# NightLightWiring.net
KiCad netlist of a schematic drawn in EAGLE
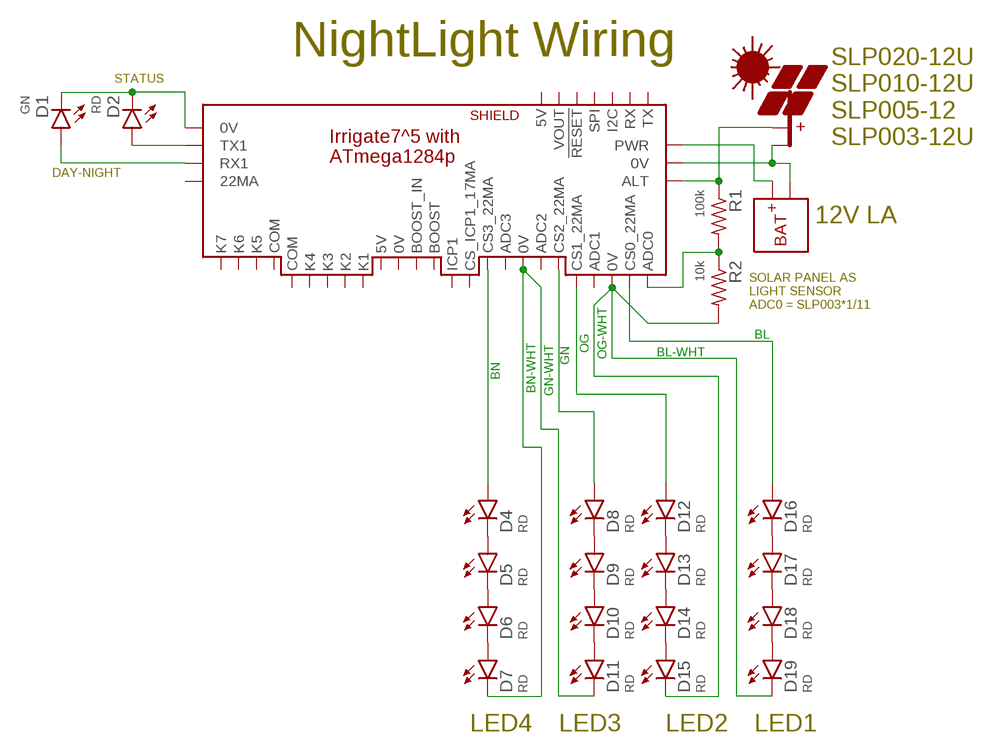
[diagram p0: schematic, sheet 1]

(export (version "E")
  (design (tool "Eeschema 10.0.6"))
  (components
    (comp (ref "D1")
      (value "GN")
      (footprint "eagle-import:LED5MM")
      (libsource (lib "eagle-import") (part "LED5MM"))
    )
    (comp (ref "D2")
      (value "RD")
      (footprint "eagle-import:LED5MM")
      (libsource (lib "eagle-import") (part "LED5MM"))
    )
    (comp (ref "D4")
      (value "RD")
      (footprint "eagle-import:LED5MM")
      (libsource (lib "eagle-import") (part "LED5MM"))
    )
    (comp (ref "D5")
      (value "RD")
      (footprint "eagle-import:LED5MM")
      (libsource (lib "eagle-import") (part "LED5MM"))
    )
    (comp (ref "D6")
      (value "RD")
      (footprint "eagle-import:LED5MM")
      (libsource (lib "eagle-import") (part "LED5MM"))
    )
    (comp (ref "D7")
      (value "RD")
      (footprint "eagle-import:LED5MM")
      (libsource (lib "eagle-import") (part "LED5MM"))
    )
    (comp (ref "D8")
      (value "RD")
      (footprint "eagle-import:LED5MM")
      (libsource (lib "eagle-import") (part "LED5MM"))
    )
    (comp (ref "D9")
      (value "RD")
      (footprint "eagle-import:LED5MM")
      (libsource (lib "eagle-import") (part "LED5MM"))
    )
    (comp (ref "D10")
      (value "RD")
      (footprint "eagle-import:LED5MM")
      (libsource (lib "eagle-import") (part "LED5MM"))
    )
    (comp (ref "D11")
      (value "RD")
      (footprint "eagle-import:LED5MM")
      (libsource (lib "eagle-import") (part "LED5MM"))
    )
    (comp (ref "D12")
      (value "RD")
      (footprint "eagle-import:LED5MM")
      (libsource (lib "eagle-import") (part "LED5MM"))
    )
    (comp (ref "D13")
      (value "RD")
      (footprint "eagle-import:LED5MM")
      (libsource (lib "eagle-import") (part "LED5MM"))
    )
    (comp (ref "D14")
      (value "RD")
      (footprint "eagle-import:LED5MM")
      (libsource (lib "eagle-import") (part "LED5MM"))
    )
    (comp (ref "D15")
      (value "RD")
      (footprint "eagle-import:LED5MM")
      (libsource (lib "eagle-import") (part "LED5MM"))
    )
    (comp (ref "D16")
      (value "RD")
      (footprint "eagle-import:LED5MM")
      (libsource (lib "eagle-import") (part "LED5MM"))
    )
    (comp (ref "D17")
      (value "RD")
      (footprint "eagle-import:LED5MM")
      (libsource (lib "eagle-import") (part "LED5MM"))
    )
    (comp (ref "D18")
      (value "RD")
      (footprint "eagle-import:LED5MM")
      (libsource (lib "eagle-import") (part "LED5MM"))
    )
    (comp (ref "D19")
      (value "RD")
      (footprint "eagle-import:LED5MM")
      (libsource (lib "eagle-import") (part "LED5MM"))
    )
    (comp (ref "PV4")
      (value "PV")
      (footprint "eagle-import:NA-30")
      (libsource (lib "eagle-import") (part "PV"))
    )
    (comp (ref "R1")
      (value "100k")
      (footprint "eagle-import:C0805(2012)")
      (libsource (lib "eagle-import") (part "R0805"))
    )
    (comp (ref "R2")
      (value "10k")
      (footprint "eagle-import:C0805(2012)")
      (libsource (lib "eagle-import") (part "R0805"))
    )
    (comp (ref "U$1")
      (value "IRRIGATE7")
      (footprint "eagle-import:WITH_RPU_NAMES")
      (libsource (lib "eagle-import") (part "IRRIGATE7"))
    )
    (comp (ref "U$7")
      (value "BAT")
      (footprint "eagle-import:NA-30")
      (libsource (lib "eagle-import") (part "BAT"))
    )
  )
  (nets
    (net (code "1") (name "/BL") (class "Default")
      (node (ref "D16") (pin "A") (pinfunction "A_A") (pintype "passive"))
      (node (ref "U$1") (pin "22MA@ADC0") (pinfunction "CS0_22MA_22MA@ADC0") (pintype "bidirectional"))
    )
    (net (code "2") (name "/BL-WHT") (class "Default")
      (node (ref "D19") (pin "K") (pinfunction "K_K") (pintype "passive"))
    )
    (net (code "3") (name "/BN") (class "Default")
      (node (ref "D4") (pin "A") (pinfunction "A_A") (pintype "passive"))
      (node (ref "U$1") (pin "22MA@ADC5") (pinfunction "CS3_22MA_22MA@ADC5") (pintype "bidirectional"))
    )
    (net (code "4") (name "/BN-WHT") (class "Default")
      (node (ref "D7") (pin "K") (pinfunction "K_K") (pintype "passive"))
    )
    (net (code "5") (name "/GN") (class "Default")
      (node (ref "D8") (pin "A") (pinfunction "A_A") (pintype "passive"))
      (node (ref "U$1") (pin "22MA@ADC4") (pinfunction "CS2_22MA_22MA@ADC4") (pintype "bidirectional"))
    )
    (net (code "6") (name "/GN-WHT") (class "Default")
      (node (ref "D11") (pin "K") (pinfunction "K_K") (pintype "passive"))
      (node (ref "U$1") (pin "ICP3") (pinfunction "0V_ICP3") (pintype "bidirectional"))
    )
    (net (code "7") (name "/OG") (class "Default")
      (node (ref "D12") (pin "A") (pinfunction "A_A") (pintype "passive"))
      (node (ref "U$1") (pin "22MA@ADC1") (pinfunction "CS1_22MA_22MA@ADC1") (pintype "bidirectional"))
    )
    (net (code "8") (name "/OG-WHT") (class "Default")
      (node (ref "D15") (pin "K") (pinfunction "K_K") (pintype "passive"))
      (node (ref "U$1") (pin "0V@ADC2") (pinfunction "0V_0V@ADC2") (pintype "bidirectional"))
    )
    (net (code "9") (name "Net-(D1-PadK)") (class "Default")
      (node (ref "D1") (pin "K") (pinfunction "K_K") (pintype "passive"))
      (node (ref "D2") (pin "K") (pinfunction "K_K") (pintype "passive"))
      (node (ref "U$1") (pin "17MA@ICP3") (pinfunction "0V_17MA@ICP3") (pintype "bidirectional"))
    )
    (net (code "10") (name "Net-(D4-PadK)") (class "Default")
      (node (ref "D4") (pin "K") (pinfunction "K_K") (pintype "passive"))
      (node (ref "D5") (pin "A") (pinfunction "A_A") (pintype "passive"))
    )
    (net (code "11") (name "Net-(D5-PadK)") (class "Default")
      (node (ref "D5") (pin "K") (pinfunction "K_K") (pintype "passive"))
      (node (ref "D6") (pin "A") (pinfunction "A_A") (pintype "passive"))
    )
    (net (code "12") (name "Net-(D6-PadK)") (class "Default")
      (node (ref "D6") (pin "K") (pinfunction "K_K") (pintype "passive"))
      (node (ref "D7") (pin "A") (pinfunction "A_A") (pintype "passive"))
    )
    (net (code "13") (name "Net-(D8-PadK)") (class "Default")
      (node (ref "D8") (pin "K") (pinfunction "K_K") (pintype "passive"))
      (node (ref "D9") (pin "A") (pinfunction "A_A") (pintype "passive"))
    )
    (net (code "14") (name "Net-(D10-PadA)") (class "Default")
      (node (ref "D10") (pin "A") (pinfunction "A_A") (pintype "passive"))
      (node (ref "D9") (pin "K") (pinfunction "K_K") (pintype "passive"))
    )
    (net (code "15") (name "Net-(D10-PadK)") (class "Default")
      (node (ref "D10") (pin "K") (pinfunction "K_K") (pintype "passive"))
      (node (ref "D11") (pin "A") (pinfunction "A_A") (pintype "passive"))
    )
    (net (code "16") (name "Net-(D12-PadK)") (class "Default")
      (node (ref "D12") (pin "K") (pinfunction "K_K") (pintype "passive"))
      (node (ref "D13") (pin "A") (pinfunction "A_A") (pintype "passive"))
    )
    (net (code "17") (name "Net-(D13-PadK)") (class "Default")
      (node (ref "D13") (pin "K") (pinfunction "K_K") (pintype "passive"))
      (node (ref "D14") (pin "A") (pinfunction "A_A") (pintype "passive"))
    )
    (net (code "18") (name "Net-(D14-PadK)") (class "Default")
      (node (ref "D14") (pin "K") (pinfunction "K_K") (pintype "passive"))
      (node (ref "D15") (pin "A") (pinfunction "A_A") (pintype "passive"))
    )
    (net (code "19") (name "Net-(D16-PadK)") (class "Default")
      (node (ref "D16") (pin "K") (pinfunction "K_K") (pintype "passive"))
      (node (ref "D17") (pin "A") (pinfunction "A_A") (pintype "passive"))
    )
    (net (code "20") (name "Net-(D17-PadK)") (class "Default")
      (node (ref "D17") (pin "K") (pinfunction "K_K") (pintype "passive"))
      (node (ref "D18") (pin "A") (pinfunction "A_A") (pintype "passive"))
    )
    (net (code "21") (name "Net-(D18-PadK)") (class "Default")
      (node (ref "D18") (pin "K") (pinfunction "K_K") (pintype "passive"))
      (node (ref "D19") (pin "A") (pinfunction "A_A") (pintype "passive"))
    )
    (net (code "22") (name "Net-(PV4-+PV)") (class "Default")
      (node (ref "PV4") (pin "1") (pinfunction "+PV_1") (pintype "bidirectional"))
      (node (ref "R1") (pin "1") (pinfunction "1_1") (pintype "passive"))
      (node (ref "U$1") (pin "AUX") (pinfunction "ALT_AUX") (pintype "bidirectional"))
    )
    (net (code "23") (name "Net-(PV4--PV)") (class "Default")
      (node (ref "PV4") (pin "2") (pinfunction "-PV_2") (pintype "bidirectional"))
      (node (ref "U$1") (pin "0V@PWR") (pinfunction "0V_0V@PWR") (pintype "bidirectional"))
      (node (ref "U$7") (pin "2") (pinfunction "-BAT_2") (pintype "bidirectional"))
    )
    (net (code "24") (name "Net-(R1-Pad2)") (class "Default")
      (node (ref "R1") (pin "2") (pinfunction "2_2") (pintype "passive"))
      (node (ref "R2") (pin "1") (pinfunction "1_1") (pintype "passive"))
      (node (ref "U$1") (pin "ADC0") (pinfunction "ADC0_ADC0") (pintype "bidirectional"))
    )
    (net (code "25") (name "Net-(U$1-RX1)") (class "Default")
      (node (ref "D1") (pin "A") (pinfunction "A_A") (pintype "passive"))
      (node (ref "U$1") (pin "DIO2") (pinfunction "RX1_DIO2") (pintype "bidirectional"))
    )
    (net (code "26") (name "Net-(U$1-TX1)") (class "Default")
      (node (ref "D2") (pin "A") (pinfunction "A_A") (pintype "passive"))
      (node (ref "U$1") (pin "DIO3") (pinfunction "TX1_DIO3") (pintype "bidirectional"))
    )
    (net (code "27") (name "Net-(U$7-+BAT)") (class "Default")
      (node (ref "U$1") (pin "PWR") (pinfunction "PWR_PWR") (pintype "bidirectional"))
      (node (ref "U$7") (pin "1") (pinfunction "+BAT_1") (pintype "bidirectional"))
    )
    (net (code "28") (name "unconnected-(R2-Pad2)") (class "Default")
      (node (ref "R2") (pin "2") (pinfunction "2_2") (pintype "passive"))
    )
    (net (code "29") (name "unconnected-(U$1-5V-PadSHLD_5V)") (class "Default")
      (node (ref "U$1") (pin "SHLD_5V") (pinfunction "5V_SHLD_5V") (pintype "bidirectional"))
    )
    (net (code "30") (name "unconnected-(U$1-22MA-Pad22MA@DIO2)") (class "Default")
      (node (ref "U$1") (pin "22MA@DIO2") (pinfunction "22MA_22MA@DIO2") (pintype "bidirectional"))
    )
    (net (code "31") (name "unconnected-(U$1-ADC2-PadADC4)") (class "Default")
      (node (ref "U$1") (pin "ADC4") (pinfunction "ADC2_ADC4") (pintype "bidirectional"))
    )
    (net (code "32") (name "unconnected-(U$1-ADC3-PadADC5)") (class "Default")
      (node (ref "U$1") (pin "ADC5") (pinfunction "ADC3_ADC5") (pintype "bidirectional"))
    )
    (net (code "33") (name "unconnected-(U$1-COM-PadCOM@K4)") (class "Default")
      (node (ref "U$1") (pin "COM@K4") (pinfunction "COM_COM@K4") (pintype "bidirectional"))
    )
    (net (code "34") (name "unconnected-(U$1-COM-PadCOM@K5)") (class "Default")
      (node (ref "U$1") (pin "COM@K5") (pinfunction "COM_COM@K5") (pintype "bidirectional"))
    )
    (net (code "35") (name "unconnected-(U$1-CS_ICP1_17MA-Pad17MA@ICP1)") (class "Default")
      (node (ref "U$1") (pin "17MA@ICP1") (pinfunction "CS_ICP1_17MA_17MA@ICP1") (pintype "bidirectional"))
    )
    (net (code "36") (name "unconnected-(U$1-Pad0V)") (class "Default")
      (node (ref "U$1") (pin "0V") (pinfunction "0V_0V") (pintype "bidirectional"))
    )
    (net (code "37") (name "unconnected-(U$1-Pad5V)") (class "Default")
      (node (ref "U$1") (pin "5V") (pinfunction "5V_5V") (pintype "bidirectional"))
    )
    (net (code "38") (name "unconnected-(U$1-PadADC1)") (class "Default")
      (node (ref "U$1") (pin "ADC1") (pinfunction "ADC1_ADC1") (pintype "bidirectional"))
    )
    (net (code "39") (name "unconnected-(U$1-PadBOOST)") (class "Default")
      (node (ref "U$1") (pin "BOOST") (pinfunction "BOOST_BOOST") (pintype "bidirectional"))
    )
    (net (code "40") (name "unconnected-(U$1-PadBOOST_IN)") (class "Default")
      (node (ref "U$1") (pin "BOOST_IN") (pinfunction "BOOST_IN_BOOST_IN") (pintype "bidirectional"))
    )
    (net (code "41") (name "unconnected-(U$1-PadI2C)") (class "Default")
      (node (ref "U$1") (pin "I2C") (pinfunction "I2C_I2C") (pintype "bidirectional"))
    )
    (net (code "42") (name "unconnected-(U$1-PadICP1)") (class "Default")
      (node (ref "U$1") (pin "ICP1") (pinfunction "ICP1_ICP1") (pintype "bidirectional"))
    )
    (net (code "43") (name "unconnected-(U$1-PadK1)") (class "Default")
      (node (ref "U$1") (pin "K1") (pinfunction "K1_K1") (pintype "bidirectional"))
    )
    (net (code "44") (name "unconnected-(U$1-PadK2)") (class "Default")
      (node (ref "U$1") (pin "K2") (pinfunction "K2_K2") (pintype "bidirectional"))
    )
    (net (code "45") (name "unconnected-(U$1-PadK3)") (class "Default")
      (node (ref "U$1") (pin "K3") (pinfunction "K3_K3") (pintype "bidirectional"))
    )
    (net (code "46") (name "unconnected-(U$1-PadK4)") (class "Default")
      (node (ref "U$1") (pin "K4") (pinfunction "K4_K4") (pintype "bidirectional"))
    )
    (net (code "47") (name "unconnected-(U$1-PadK5)") (class "Default")
      (node (ref "U$1") (pin "K5") (pinfunction "K5_K5") (pintype "bidirectional"))
    )
    (net (code "48") (name "unconnected-(U$1-PadK6)") (class "Default")
      (node (ref "U$1") (pin "K6") (pinfunction "K6_K6") (pintype "bidirectional"))
    )
    (net (code "49") (name "unconnected-(U$1-PadK7)") (class "Default")
      (node (ref "U$1") (pin "K7") (pinfunction "K7_K7") (pintype "bidirectional"))
    )
    (net (code "50") (name "unconnected-(U$1-PadRX)") (class "Default")
      (node (ref "U$1") (pin "RX") (pinfunction "RX_RX") (pintype "bidirectional"))
    )
    (net (code "51") (name "unconnected-(U$1-PadSPI)") (class "Default")
      (node (ref "U$1") (pin "SPI") (pinfunction "SPI_SPI") (pintype "bidirectional"))
    )
    (net (code "52") (name "unconnected-(U$1-PadTX)") (class "Default")
      (node (ref "U$1") (pin "TX") (pinfunction "TX_TX") (pintype "bidirectional"))
    )
    (net (code "53") (name "unconnected-(U$1-VOUT-PadSHLD_VOUT)") (class "Default")
      (node (ref "U$1") (pin "SHLD_VOUT") (pinfunction "VOUT_SHLD_VOUT") (pintype "bidirectional"))
    )
    (net (code "54") (name "unconnected-(U$1-~{RESET}-Pad!RESET)") (class "Default")
      (node (ref "U$1") (pin "!RESET") (pinfunction "~{RESET}_!RESET") (pintype "bidirectional"))
    )
  )
)
